# HANDS_FREE_Power_Manager_V1.net
KiCad netlist of a schematic drawn in Altium Designer
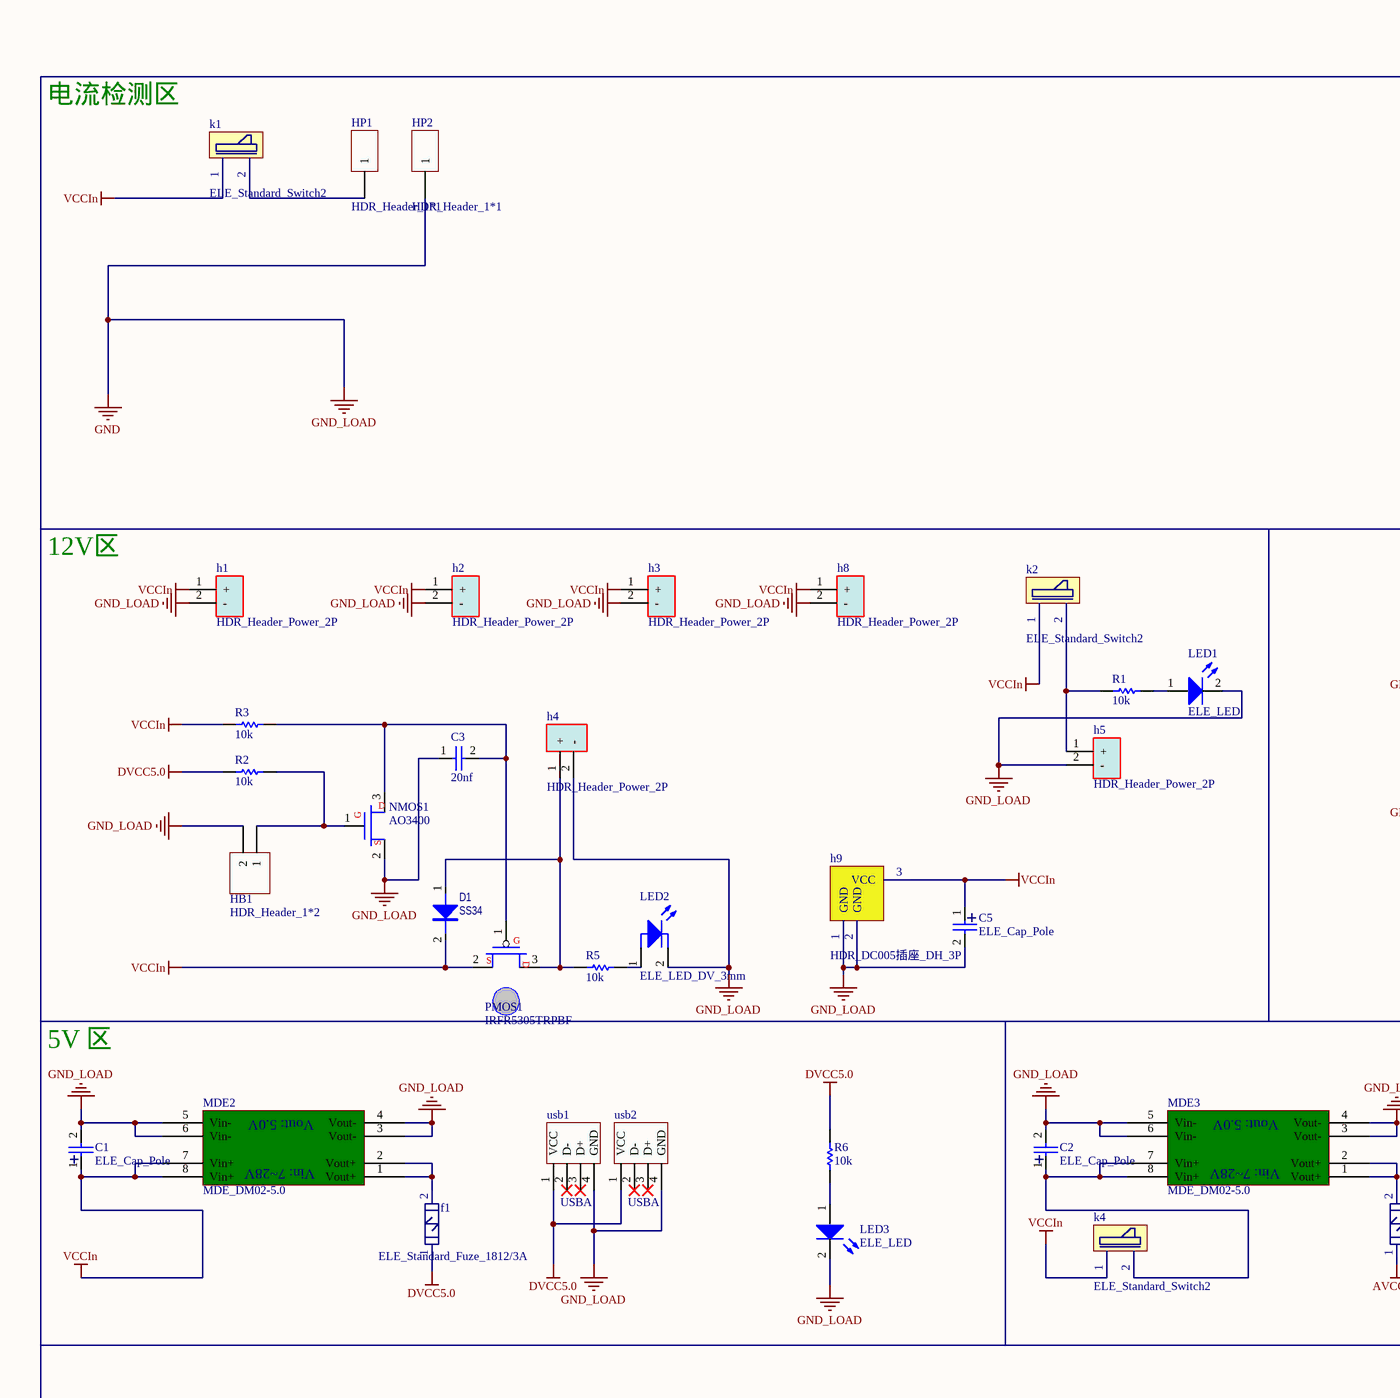
[diagram p0: HANDS_FREE_Power_Manager_V1.SchDoc, left]
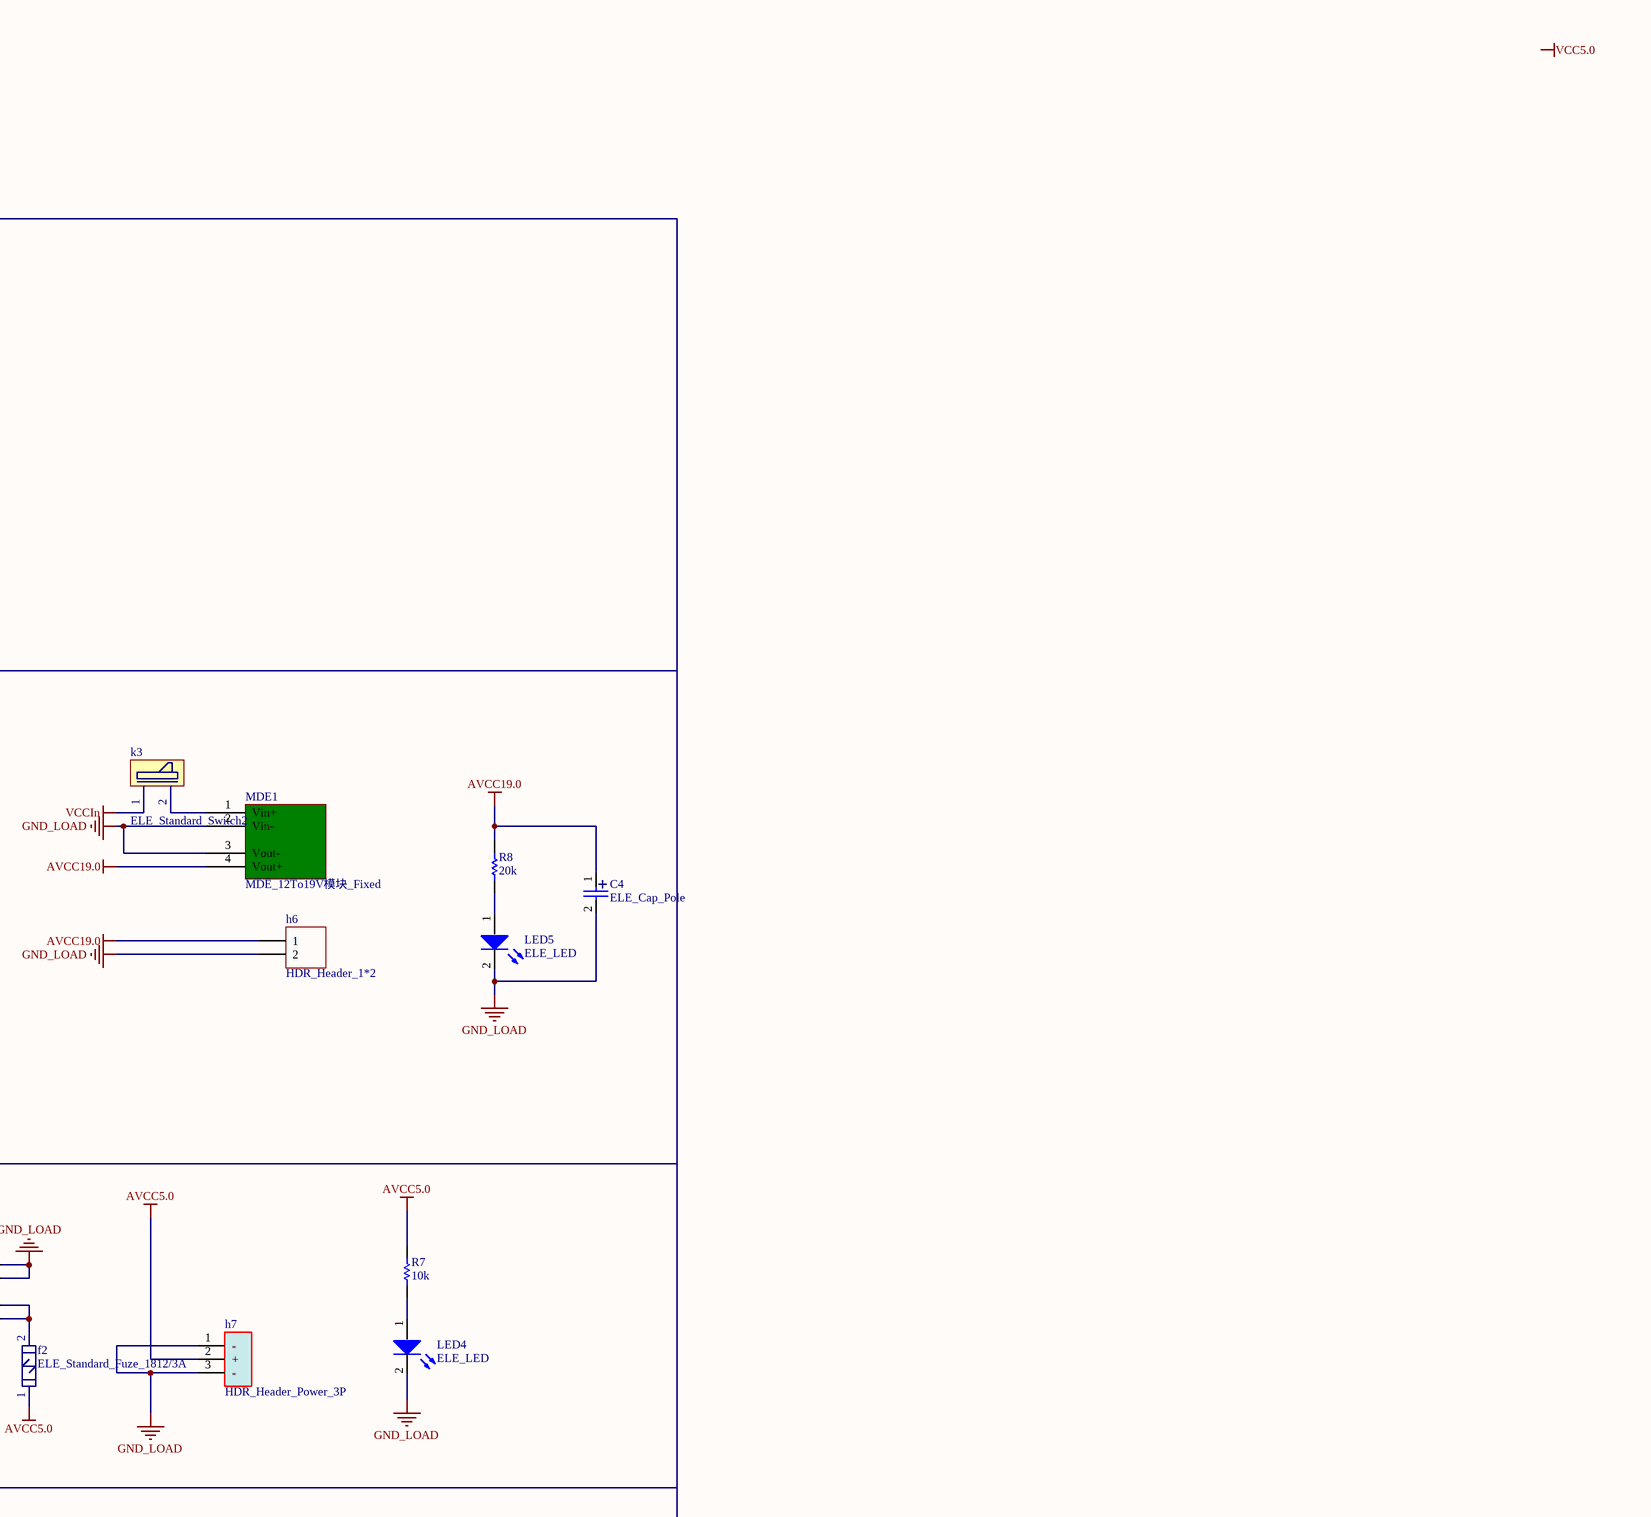
[diagram p1: HANDS_FREE_Power_Manager_V1.SchDoc, right]

(export (version "E")
  (design (tool "Eeschema 10.0.6"))
  (components
    (comp (ref "C1")
      (value "ELE_Cap_Pole")
      (footprint "ELE_铝解电容_PV_6.3")
      (description "贴片 极性电容 0603")
      (libsource (lib "Hands_free") (part "ELE_Cap_Pole"))
    )
    (comp (ref "C2")
      (value "ELE_Cap_Pole")
      (footprint "ELE_铝解电容_PV_6.3")
      (description "贴片 极性电容 0603")
      (libsource (lib "Hands_free") (part "ELE_Cap_Pole"))
    )
    (comp (ref "C3")
      (value "20nf")
      (footprint "ELE_0603_P")
      (description "贴片 电容 0603")
      (libsource (lib "Hands_free") (part "ELE_Cap"))
    )
    (comp (ref "C4")
      (value "ELE_Cap_Pole")
      (footprint "ELE_铝解电容_PV_6.3")
      (description "贴片 极性电容 0603")
      (libsource (lib "Hands_free") (part "ELE_Cap_Pole"))
    )
    (comp (ref "C5")
      (value "ELE_Cap_Pole")
      (footprint "ELE_铝解电容_PV_6.3")
      (description "贴片 极性电容 0603")
      (libsource (lib "Hands_free") (part "ELE_Cap_Pole"))
    )
    (comp (ref "D1")
      (value "SS34")
      (footprint "ELE_D1206")
      (description "贴片 二极管 1206")
      (libsource (lib "Hands_free") (part "ELE_Diode"))
    )
    (comp (ref "f1")
      (value "ELE_Standard_Fuze_1812/3A")
      (footprint "ELE_FUZE_1812")
      (description "贴片保险丝 1812 3A")
      (libsource (lib "Hands_free") (part "ELE_Standard_Fuze_1812/3A"))
    )
    (comp (ref "f2")
      (value "ELE_Standard_Fuze_1812/3A")
      (footprint "ELE_FUZE_1812")
      (description "贴片保险丝 1812 3A")
      (libsource (lib "Hands_free") (part "ELE_Standard_Fuze_1812/3A"))
    )
    (comp (ref "h1")
      (value "HDR_Header_Power_2P")
      (footprint "HDR_MOLEX_POWER5557_DH_2P")
      (description "直插 5557接头 1*2P")
      (libsource (lib "Hands_free") (part "HDR_Header_Power_2P"))
    )
    (comp (ref "h2")
      (value "HDR_Header_Power_2P")
      (footprint "HDR_MOLEX_POWER5557_DH_2P")
      (description "直插 5557接头 1*2P")
      (libsource (lib "Hands_free") (part "HDR_Header_Power_2P"))
    )
    (comp (ref "h3")
      (value "HDR_Header_Power_2P")
      (footprint "HDR_MOLEX_POWER5557_DH_2P")
      (description "直插 5557接头 1*2P")
      (libsource (lib "Hands_free") (part "HDR_Header_Power_2P"))
    )
    (comp (ref "h4")
      (value "HDR_Header_Power_2P")
      (footprint "HDR_MOLEX_POWER5557_DH_2P")
      (description "直插 5557接头 1*2P")
      (libsource (lib "") (part "HDR_Header_Power_2P_1"))
    )
    (comp (ref "h5")
      (value "HDR_Header_Power_2P")
      (footprint "HDR_MOLEX_CANMX3.0_DH_2P")
      (description "直插 5557接头 1*2P")
      (libsource (lib "Hands_free") (part "HDR_Header_Power_2P"))
    )
    (comp (ref "h6")
      (value "HDR_Header_1*2")
      (footprint "HDR_KF300_DH_2P")
      (fields (field (name "PUBLISHER") "Altium Limited"))
      (libsource (lib "") (part "HDR_Header_1*2_1"))
    )
    (comp (ref "h7")
      (value "HDR_Header_Power_3P")
      (footprint "HDR_Header_XH2.54_DH_1*3")
      (description "5V专用 直插 XH2.54 3P接头")
      (libsource (lib "Hands_free") (part "HDR_Header_Power_3P"))
    )
    (comp (ref "h8")
      (value "HDR_Header_Power_2P")
      (footprint "HDR_MOLEX_POWER5557_DH_2P")
      (description "直插 5557接头 1*2P")
      (libsource (lib "Hands_free") (part "HDR_Header_Power_2P"))
    )
    (comp (ref "h9")
      (value "HDR_DC005插座_DH_3P")
      (footprint "ELE_DC005插座_DV")
      (description "直插 DC5.0接头")
      (libsource (lib "Hands_free") (part "HDR_DC005插座_DH_3P"))
    )
    (comp (ref "HB1")
      (value "HDR_Header_1*2")
      (footprint "HDR_Header_2.00_DH_1*2")
      (fields (field (name "PUBLISHER") "Altium Limited"))
      (libsource (lib "Hands_free") (part "HDR_Header_1*2"))
    )
    (comp (ref "HP1")
      (value "HDR_Header_1*1")
      (footprint "HDR_H_DH_1P")
      (fields (field (name "PUBLISHER") "Altium Limited"))
      (libsource (lib "Hands_free") (part "HDR_Header_1*1"))
    )
    (comp (ref "HP2")
      (value "HDR_Header_1*1")
      (footprint "HDR_H_DH_1P")
      (fields (field (name "PUBLISHER") "Altium Limited"))
      (libsource (lib "Hands_free") (part "HDR_Header_1*1"))
    )
    (comp (ref "k1")
      (value "ELE_Standard_Switch2")
      (footprint "ELE_船型开关2_D")
      (description "直插 船型开关 2脚 8.5*13.5mm")
      (libsource (lib "Hands_free") (part "ELE_Standard_Switch2"))
    )
    (comp (ref "k2")
      (value "ELE_Standard_Switch2")
      (footprint "ELE_船型开关1_D")
      (description "直插 船型开关 2脚 8.5*13.5mm")
      (libsource (lib "Hands_free") (part "ELE_Standard_Switch2"))
    )
    (comp (ref "k3")
      (value "ELE_Standard_Switch2")
      (footprint "ELE_船型开关1_D")
      (description "直插 船型开关 2脚 8.5*13.5mm")
      (libsource (lib "Hands_free") (part "ELE_Standard_Switch2"))
    )
    (comp (ref "k4")
      (value "ELE_Standard_Switch2")
      (footprint "ELE_船型开关1_D")
      (description "直插 船型开关 2脚 8.5*13.5mm")
      (libsource (lib "Hands_free") (part "ELE_Standard_Switch2"))
    )
    (comp (ref "LED1")
      (value "ELE_LED")
      (footprint "ELE_0603极性_P")
      (description "发光二极管 0603")
      (fields (field (name "PUBLISHER") "Altium Limited"))
      (libsource (lib "Hands_free") (part "ELE_LED"))
    )
    (comp (ref "LED2")
      (value "ELE_LED_DV_3mm")
      (footprint "ELE_LED_DV")
      (description "发光二极管 直插 3mm")
      (fields (field (name "PUBLISHER") "Altium Limited"))
      (libsource (lib "Hands_free") (part "ELE_LED_DV_3mm"))
    )
    (comp (ref "LED3")
      (value "ELE_LED")
      (footprint "ELE_0603极性_P")
      (description "发光二极管 0603")
      (fields (field (name "PUBLISHER") "Altium Limited"))
      (libsource (lib "Hands_free") (part "ELE_LED"))
    )
    (comp (ref "LED4")
      (value "ELE_LED")
      (footprint "ELE_0603极性_P")
      (description "发光二极管 0603")
      (fields (field (name "PUBLISHER") "Altium Limited"))
      (libsource (lib "Hands_free") (part "ELE_LED"))
    )
    (comp (ref "LED5")
      (value "ELE_LED")
      (footprint "ELE_0603极性_P")
      (description "发光二极管 0603")
      (fields (field (name "PUBLISHER") "Altium Limited"))
      (libsource (lib "Hands_free") (part "ELE_LED"))
    )
    (comp (ref "MDE1")
      (value "MDE_12To19V模块_Fixed")
      (footprint "MDE_12To19V模块_Fixed")
      (description "19V升压模块， 车载电源模块。")
      (libsource (lib "Hands_free") (part "MDE_12To19V模块_Fixed"))
    )
    (comp (ref "MDE2")
      (value "MDE_DM02-5.0")
      (footprint "MDE_DM02-5.0")
      (libsource (lib "Hands_free") (part "MDE_DM02-5.0"))
    )
    (comp (ref "MDE3")
      (value "MDE_DM02-5.0")
      (footprint "MDE_DM02-5.0")
      (libsource (lib "Hands_free") (part "MDE_DM02-5.0"))
    )
    (comp (ref "NMOS1")
      (value "AO3400")
      (footprint "CHP_SOT23_P_3P")
      (description "贴片 NMOS管 SOT23")
      (fields (field (name "PUBLISHER") "Altium Limited"))
      (libsource (lib "Hands_free") (part "ELE_NMOS_1"))
    )
    (comp (ref "PMOS1")
      (value "IRFR5305TRPBF")
      (footprint "CHP_TOD252")
      (description "贴片 PMOS管 SOT23")
      (fields (field (name "PUBLISHER") "Altium Limited"))
      (libsource (lib "Hands_free") (part "ELE_PMOS_1"))
    )
    (comp (ref "R1")
      (value "10k")
      (footprint "ELE_0603_P")
      (description "贴片 电阻50欧 0603")
      (libsource (lib "Hands_free") (part "ELE_Standard_R50R"))
    )
    (comp (ref "R2")
      (value "10k")
      (footprint "ELE_0603_P")
      (description "贴片 电阻50欧 0603")
      (libsource (lib "Hands_free") (part "ELE_Standard_R50R"))
    )
    (comp (ref "R3")
      (value "10k")
      (footprint "ELE_0603_P")
      (description "贴片 电阻50欧 0603")
      (libsource (lib "Hands_free") (part "ELE_Standard_R50R"))
    )
    (comp (ref "R5")
      (value "10k")
      (footprint "ELE_0603_P")
      (description "贴片 电阻50欧 0603")
      (libsource (lib "Hands_free") (part "ELE_Standard_R50R"))
    )
    (comp (ref "R6")
      (value "10k")
      (footprint "ELE_0603_P")
      (description "贴片 电阻50欧 0603")
      (libsource (lib "Hands_free") (part "ELE_Standard_R50R"))
    )
    (comp (ref "R7")
      (value "10k")
      (footprint "ELE_0603_P")
      (description "贴片 电阻50欧 0603")
      (libsource (lib "Hands_free") (part "ELE_Standard_R50R"))
    )
    (comp (ref "R8")
      (value "20k")
      (footprint "ELE_0603_P")
      (description "贴片 电阻50欧 0603")
      (libsource (lib "Hands_free") (part "ELE_Standard_R50R"))
    )
    (comp (ref "usb1")
      (value "USBA")
      (footprint "HDR_USBA_DH")
      (description "直插 USB头")
      (libsource (lib "Hands_free") (part "HDR_USB_HOST"))
    )
    (comp (ref "usb2")
      (value "USBA")
      (footprint "HDR_USBA_DH")
      (description "直插 USB头")
      (libsource (lib "Hands_free") (part "HDR_USB_HOST"))
    )
  )
  (nets
    (net (code "1") (name "AVCC5.0") (class "Default")
      (node (ref "R7") (pin "2") (pinfunction "2_2") (pintype "passive"))
      (node (ref "f2") (pin "1") (pintype "passive"))
      (node (ref "h7") (pin "2") (pinfunction "+_2") (pintype "passive"))
    )
    (net (code "2") (name "AVCC19.0") (class "Default")
      (node (ref "C4") (pin "1") (pintype "passive"))
      (node (ref "MDE1") (pin "4") (pinfunction "Vout+_4") (pintype "passive"))
      (node (ref "R8") (pin "2") (pinfunction "2_2") (pintype "passive"))
      (node (ref "h6") (pin "1") (pinfunction "1_1") (pintype "passive"))
    )
    (net (code "3") (name "DVCC5.0") (class "Default")
      (node (ref "R2") (pin "1") (pinfunction "1_1") (pintype "passive"))
      (node (ref "R6") (pin "2") (pinfunction "2_2") (pintype "passive"))
      (node (ref "f1") (pin "1") (pintype "passive"))
      (node (ref "usb1") (pin "1") (pinfunction "VCC_1") (pintype "passive"))
      (node (ref "usb2") (pin "1") (pinfunction "VCC_1") (pintype "passive"))
    )
    (net (code "4") (name "GND") (class "Default")
      (node (ref "C1") (pin "2") (pintype "passive"))
      (node (ref "C2") (pin "2") (pintype "passive"))
      (node (ref "C3") (pin "1") (pintype "passive"))
      (node (ref "C4") (pin "2") (pintype "passive"))
      (node (ref "C5") (pin "2") (pintype "passive"))
      (node (ref "HB1") (pin "2") (pinfunction "2_2") (pintype "passive"))
      (node (ref "HP2") (pin "1") (pinfunction "1_1") (pintype "passive"))
      (node (ref "LED1") (pin "2") (pintype "passive"))
      (node (ref "LED2") (pin "2") (pintype "passive"))
      (node (ref "LED3") (pin "2") (pintype "passive"))
      (node (ref "LED4") (pin "2") (pintype "passive"))
      (node (ref "LED5") (pin "2") (pintype "passive"))
      (node (ref "MDE1") (pin "2") (pinfunction "Vin-_2") (pintype "passive"))
      (node (ref "MDE1") (pin "3") (pinfunction "Vout-_3") (pintype "passive"))
      (node (ref "MDE2") (pin "3") (pinfunction "Vout-_3") (pintype "passive"))
      (node (ref "MDE2") (pin "4") (pinfunction "Vout-_4") (pintype "passive"))
      (node (ref "MDE2") (pin "5") (pinfunction "Vin-_5") (pintype "passive"))
      (node (ref "MDE2") (pin "6") (pinfunction "Vin-_6") (pintype "passive"))
      (node (ref "MDE3") (pin "3") (pinfunction "Vout-_3") (pintype "passive"))
      (node (ref "MDE3") (pin "4") (pinfunction "Vout-_4") (pintype "passive"))
      (node (ref "MDE3") (pin "5") (pinfunction "Vin-_5") (pintype "passive"))
      (node (ref "MDE3") (pin "6") (pinfunction "Vin-_6") (pintype "passive"))
      (node (ref "NMOS1") (pin "2") (pinfunction "S_2") (pintype "passive"))
      (node (ref "h1") (pin "2") (pinfunction "-_2") (pintype "passive"))
      (node (ref "h2") (pin "2") (pinfunction "-_2") (pintype "passive"))
      (node (ref "h3") (pin "2") (pinfunction "-_2") (pintype "passive"))
      (node (ref "h4") (pin "2") (pinfunction "-_2") (pintype "passive"))
      (node (ref "h5") (pin "2") (pinfunction "-_2") (pintype "passive"))
      (node (ref "h6") (pin "2") (pinfunction "2_2") (pintype "passive"))
      (node (ref "h7") (pin "1") (pinfunction "-_1") (pintype "passive"))
      (node (ref "h7") (pin "3") (pinfunction "-_3") (pintype "passive"))
      (node (ref "h8") (pin "2") (pinfunction "-_2") (pintype "passive"))
      (node (ref "h9") (pin "1") (pinfunction "GND_1") (pintype "passive"))
      (node (ref "h9") (pin "2") (pinfunction "GND_2") (pintype "passive"))
      (node (ref "usb1") (pin "4") (pinfunction "GND_4") (pintype "passive"))
      (node (ref "usb2") (pin "4") (pinfunction "GND_4") (pintype "passive"))
    )
    (net (code "5") (name "Net-(C2-Pad1)") (class "Default")
      (node (ref "C2") (pin "1") (pintype "passive"))
      (node (ref "MDE3") (pin "7") (pinfunction "Vin+_7") (pintype "passive"))
      (node (ref "MDE3") (pin "8") (pinfunction "Vin+_8") (pintype "passive"))
      (node (ref "k4") (pin "2") (pintype "passive"))
    )
    (net (code "6") (name "Net-(HP1-Pad1)") (class "Default")
      (node (ref "HP1") (pin "1") (pinfunction "1_1") (pintype "passive"))
      (node (ref "k1") (pin "2") (pintype "passive"))
    )
    (net (code "7") (name "Net-(LED1-Pad1)") (class "Default")
      (node (ref "LED1") (pin "1") (pintype "passive"))
      (node (ref "R1") (pin "2") (pinfunction "2_2") (pintype "passive"))
    )
    (net (code "8") (name "Net-(LED2-Pad1)") (class "Default")
      (node (ref "LED2") (pin "1") (pintype "passive"))
      (node (ref "R5") (pin "2") (pinfunction "2_2") (pintype "passive"))
    )
    (net (code "9") (name "Net-(LED3-Pad1)") (class "Default")
      (node (ref "LED3") (pin "1") (pintype "passive"))
      (node (ref "R6") (pin "1") (pinfunction "1_1") (pintype "passive"))
    )
    (net (code "10") (name "Net-(LED4-Pad1)") (class "Default")
      (node (ref "LED4") (pin "1") (pintype "passive"))
      (node (ref "R7") (pin "1") (pinfunction "1_1") (pintype "passive"))
    )
    (net (code "11") (name "Net-(LED5-Pad1)") (class "Default")
      (node (ref "LED5") (pin "1") (pintype "passive"))
      (node (ref "R8") (pin "1") (pinfunction "1_1") (pintype "passive"))
    )
    (net (code "12") (name "Net-(MDE1-Vin+)") (class "Default")
      (node (ref "MDE1") (pin "1") (pinfunction "Vin+_1") (pintype "passive"))
      (node (ref "k3") (pin "2") (pintype "passive"))
    )
    (net (code "13") (name "Net-(MDE2-Vout+-Pad1)") (class "Default")
      (node (ref "MDE2") (pin "1") (pinfunction "Vout+_1") (pintype "passive"))
      (node (ref "MDE2") (pin "2") (pinfunction "Vout+_2") (pintype "passive"))
      (node (ref "f1") (pin "2") (pintype "passive"))
    )
    (net (code "14") (name "Net-(MDE3-Vout+-Pad1)") (class "Default")
      (node (ref "MDE3") (pin "1") (pinfunction "Vout+_1") (pintype "passive"))
      (node (ref "MDE3") (pin "2") (pinfunction "Vout+_2") (pintype "passive"))
      (node (ref "f2") (pin "2") (pintype "passive"))
    )
    (net (code "15") (name "Net-(NMOS1-D)") (class "Default")
      (node (ref "C3") (pin "2") (pintype "passive"))
      (node (ref "NMOS1") (pin "3") (pinfunction "D_3") (pintype "passive"))
      (node (ref "PMOS1") (pin "1") (pinfunction "G_1") (pintype "passive"))
      (node (ref "R3") (pin "2") (pinfunction "2_2") (pintype "passive"))
    )
    (net (code "16") (name "Net-(NMOS1-G)") (class "Default")
      (node (ref "HB1") (pin "1") (pinfunction "1_1") (pintype "passive"))
      (node (ref "NMOS1") (pin "1") (pinfunction "G_1") (pintype "passive"))
      (node (ref "R2") (pin "2") (pinfunction "2_2") (pintype "passive"))
    )
    (net (code "17") (name "Net-(PMOS1-D)") (class "Default")
      (node (ref "D1") (pin "1") (pintype "passive"))
      (node (ref "PMOS1") (pin "3") (pinfunction "D_3") (pintype "passive"))
      (node (ref "R5") (pin "1") (pinfunction "1_1") (pintype "passive"))
      (node (ref "h4") (pin "1") (pinfunction "+_1") (pintype "passive"))
    )
    (net (code "18") (name "Net-(h5-+)") (class "Default")
      (node (ref "R1") (pin "1") (pinfunction "1_1") (pintype "passive"))
      (node (ref "h5") (pin "1") (pinfunction "+_1") (pintype "passive"))
      (node (ref "k2") (pin "2") (pintype "passive"))
    )
    (net (code "20") (name "VCCIn") (class "Default")
      (node (ref "C1") (pin "1") (pintype "passive"))
      (node (ref "C5") (pin "1") (pintype "passive"))
      (node (ref "D1") (pin "2") (pintype "passive"))
      (node (ref "MDE2") (pin "7") (pinfunction "Vin+_7") (pintype "passive"))
      (node (ref "MDE2") (pin "8") (pinfunction "Vin+_8") (pintype "passive"))
      (node (ref "PMOS1") (pin "2") (pinfunction "S_2") (pintype "passive"))
      (node (ref "R3") (pin "1") (pinfunction "1_1") (pintype "passive"))
      (node (ref "h1") (pin "1") (pinfunction "+_1") (pintype "passive"))
      (node (ref "h2") (pin "1") (pinfunction "+_1") (pintype "passive"))
      (node (ref "h3") (pin "1") (pinfunction "+_1") (pintype "passive"))
      (node (ref "h8") (pin "1") (pinfunction "+_1") (pintype "passive"))
      (node (ref "h9") (pin "3") (pinfunction "VCC_3") (pintype "passive"))
      (node (ref "k1") (pin "1") (pintype "passive"))
      (node (ref "k2") (pin "1") (pintype "passive"))
      (node (ref "k3") (pin "1") (pintype "passive"))
      (node (ref "k4") (pin "1") (pintype "passive"))
    )
    (net (code "21") (name "unconnected-(usb1-D+-Pad3)") (class "Default")
      (node (ref "usb1") (pin "3") (pinfunction "D+_3") (pintype "passive+no_connect"))
    )
    (net (code "22") (name "unconnected-(usb1-D--Pad2)") (class "Default")
      (node (ref "usb1") (pin "2") (pinfunction "D-_2") (pintype "passive+no_connect"))
    )
    (net (code "23") (name "unconnected-(usb2-D+-Pad3)") (class "Default")
      (node (ref "usb2") (pin "3") (pinfunction "D+_3") (pintype "passive+no_connect"))
    )
    (net (code "24") (name "unconnected-(usb2-D--Pad2)") (class "Default")
      (node (ref "usb2") (pin "2") (pinfunction "D-_2") (pintype "passive+no_connect"))
    )
  )
)
